# MODEM_power.net
KiCad netlist of a schematic drawn in Altium Designer
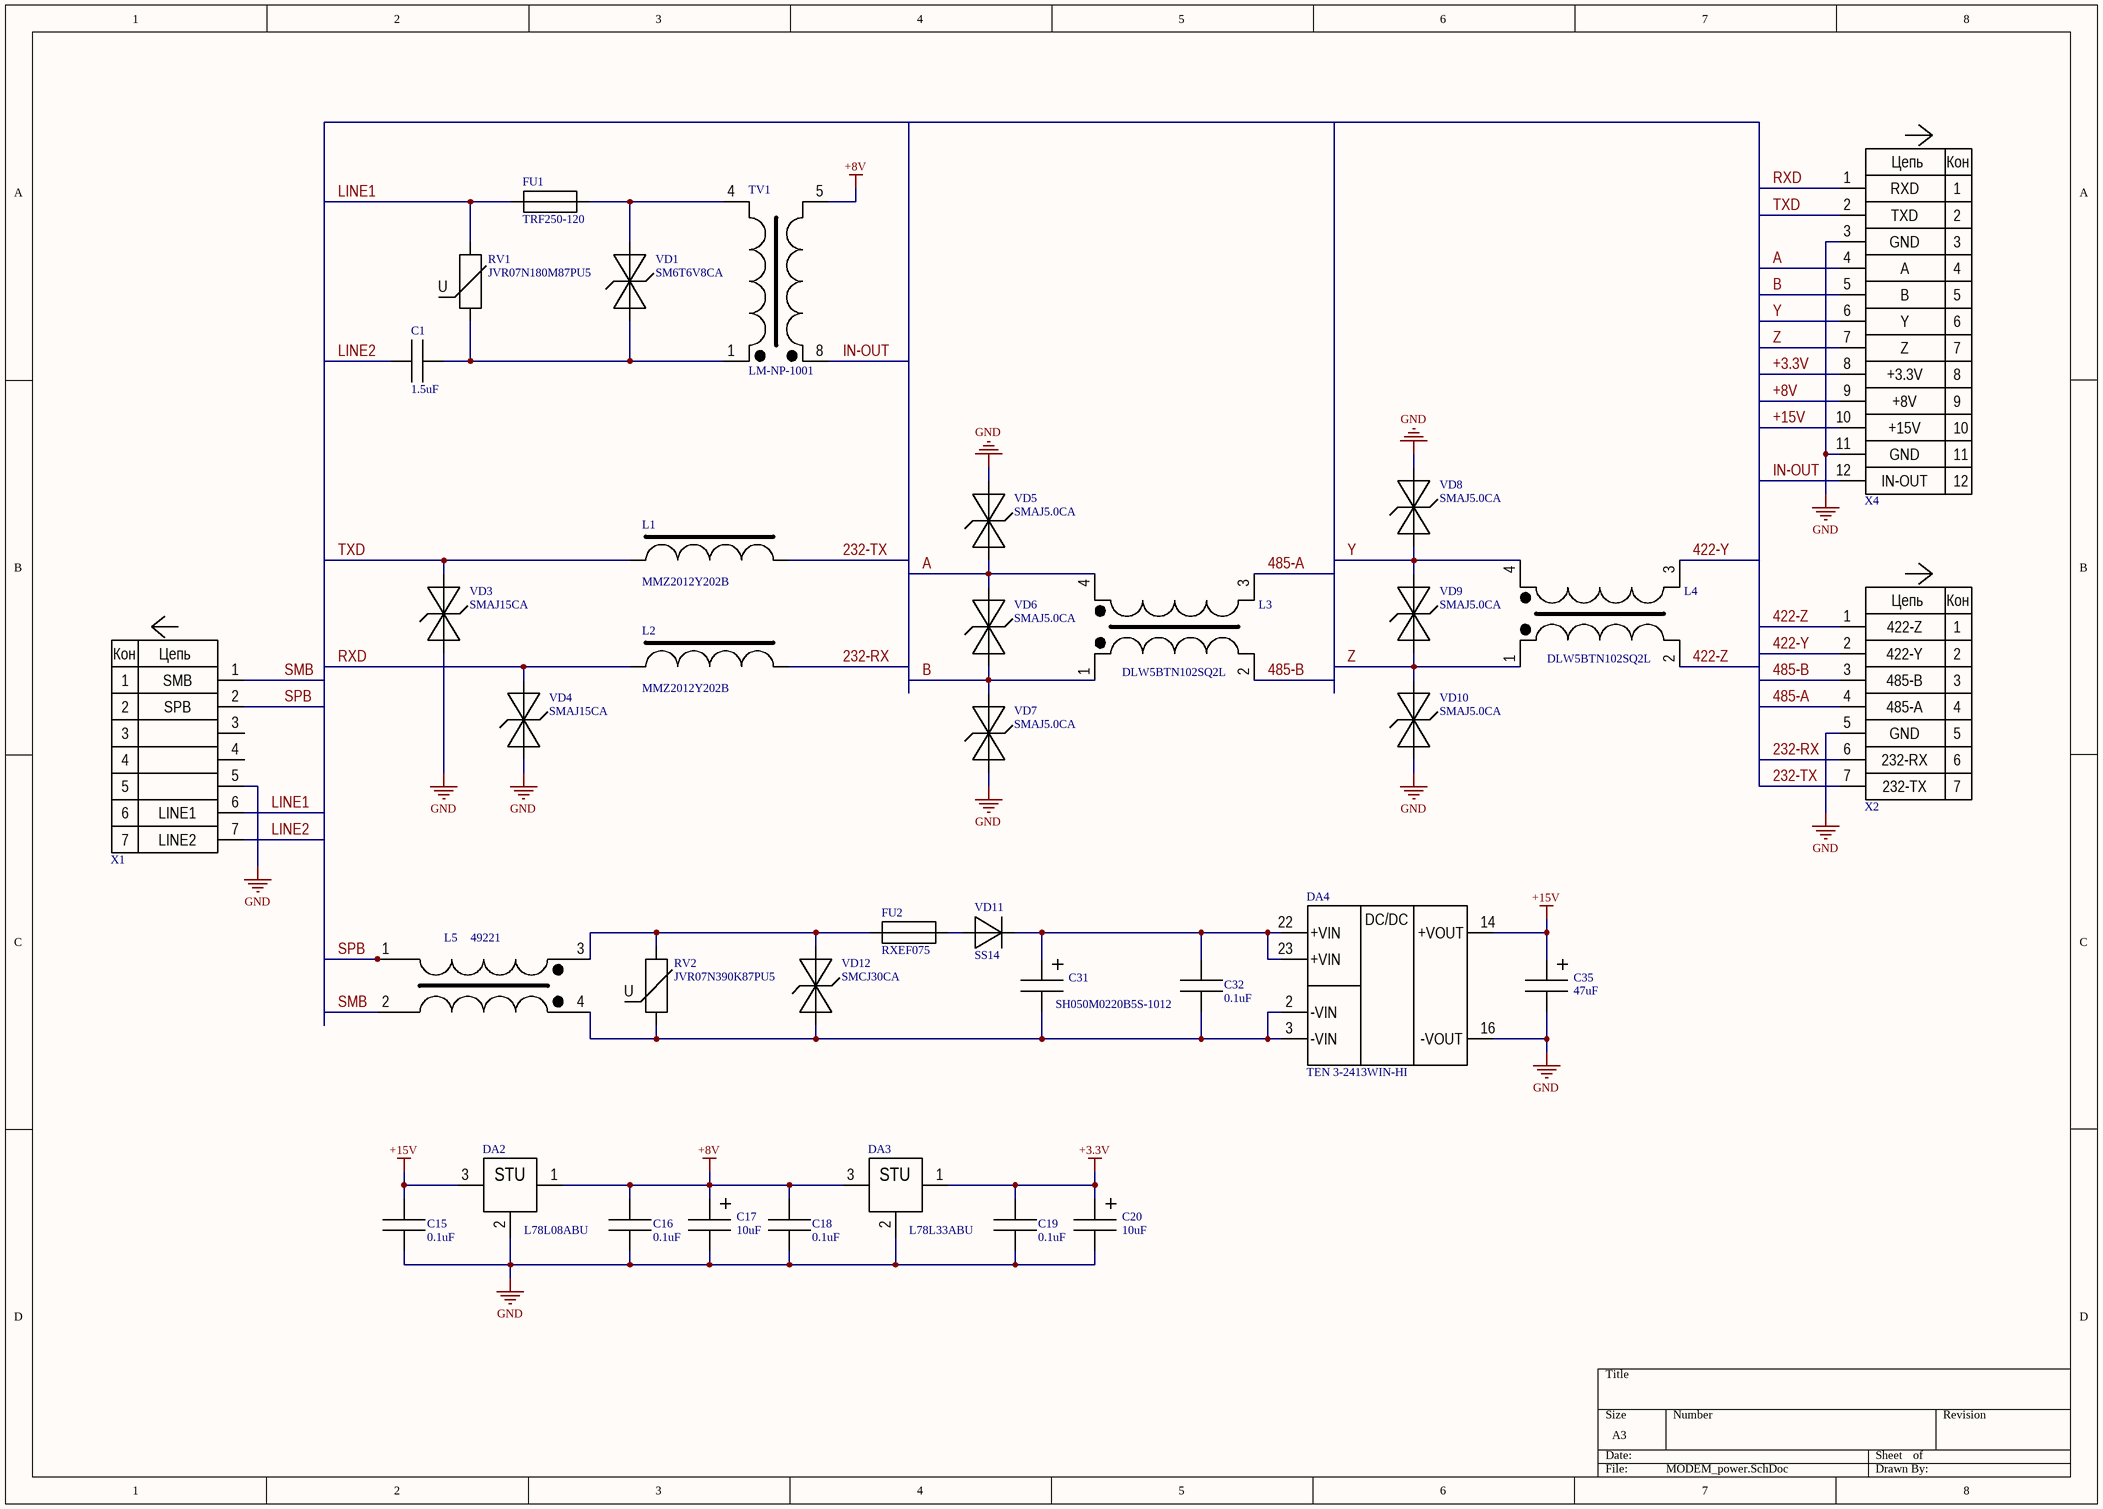
[diagram p0: MODEM_power.SchDoc]

(export (version "E")
  (design (tool "Eeschema 10.0.6"))
  (components
    (comp (ref "C1") (value "1.5uF") (footprint "TS02-22.5-h") (libsource (lib "CAPACITORS") (part "CC1206")))
    (comp (ref "C15") (value "0.1uF") (footprint "CC0805") (libsource (lib "CAPACITORS") (part "CC1206")))
    (comp (ref "C16") (value "0.1uF") (footprint "CC0805") (libsource (lib "CAPACITORS") (part "CC1206")))
    (comp (ref "C17") (value "10uF") (footprint "SMB") (libsource (lib "CAPACITORS") (part "SR-6")))
    (comp (ref "C18") (value "0.1uF") (footprint "CC0805") (libsource (lib "CAPACITORS") (part "CC1206")))
    (comp (ref "C19") (value "0.1uF") (footprint "CC0805") (libsource (lib "CAPACITORS") (part "CC1206")))
    (comp (ref "C20") (value "10uF") (footprint "SMB") (libsource (lib "CAPACITORS") (part "SR-6")))
    (comp (ref "C31")
      (value "SH050M0220B5S-1012")
      (footprint "Discr:SH050-1019")
      (libsource (lib "CAPACITORS") (part "SR-6"))
    )
    (comp (ref "C32") (value "0.1uF") (footprint "CC0805") (libsource (lib "CAPACITORS") (part "CC1206")))
    (comp (ref "C35") (value "47uF") (footprint "SMD") (libsource (lib "CAPACITORS") (part "SR-6")))
    (comp (ref "DA2") (value "L78L08ABU") (footprint "SOT-89") (libsource (lib "IC") (part "L78L08ABU")))
    (comp (ref "DA3") (value "L78L33ABU") (footprint "SOT-89") (libsource (lib "IC") (part "L78L33ABU")))
    (comp (ref "DA4")
      (value "TEN 3-2413WIN-HI")
      (footprint "TEN3-2412WIN")
      (libsource (lib "Power Supplies") (part "TEN3-2412WIN"))
    )
    (comp (ref "FU1")
      (value "TRF250-120")
      (footprint "TRF250-120")
      (libsource (lib "Discr") (part "TRF250-120"))
    )
    (comp (ref "FU2") (value "RXEF075") (footprint "RXEF075") (libsource (lib "Discr") (part "TRF250-120")))
    (comp (ref "L1")
      (value "MMZ2012Y202B")
      (footprint "MMZ2012Y202B")
      (libsource (lib "INDUCTORS") (part "MMZ2012Y202B"))
    )
    (comp (ref "L2")
      (value "MMZ2012Y202B")
      (footprint "MMZ2012Y202B")
      (libsource (lib "INDUCTORS") (part "MMZ2012Y202B"))
    )
    (comp (ref "L3")
      (value "DLW5BTN102SQ2L")
      (footprint "DLW5BTN")
      (libsource (lib "INDUCTORS") (part "DLW31SN"))
    )
    (comp (ref "L4")
      (value "DLW5BTN102SQ2L")
      (footprint "DLW5BTN")
      (libsource (lib "INDUCTORS") (part "DLW31SN"))
    )
    (comp (ref "L5") (value "49221") (footprint "49221") (libsource (lib "INDUCTORS") (part "49221")))
    (comp (ref "RV1")
      (value "JVR07N180M87PU5")
      (footprint "JVR07N330")
      (libsource (lib "Discr") (part "JVR14N361"))
    )
    (comp (ref "RV2")
      (value "JVR07N390K87PU5")
      (footprint "JVR07N330")
      (libsource (lib "Discr") (part "JVR14N361"))
    )
    (comp (ref "TV1")
      (value "LM-NP-1001")
      (footprint "LM-NP-1001")
      (libsource (lib "INDUCTORS") (part "LM-NP-1001"))
    )
    (comp (ref "VD1")
      (value "SM6T6V8CA")
      (footprint "SM6T6V8CA")
      (libsource (lib "DIODES") (part "SM6T6V8CA"))
    )
    (comp (ref "VD3")
      (value "SMAJ15CA")
      (footprint "SMAJ6.0CA")
      (libsource (lib "DIODES") (part "SMAJ6.0CA"))
    )
    (comp (ref "VD4")
      (value "SMAJ15CA")
      (footprint "SMAJ6.0CA")
      (libsource (lib "DIODES") (part "SMAJ6.0CA"))
    )
    (comp (ref "VD5")
      (value "SMAJ5.0CA")
      (footprint "SMAJ6.0CA")
      (libsource (lib "DIODES") (part "SMAJ6.0CA"))
    )
    (comp (ref "VD6")
      (value "SMAJ5.0CA")
      (footprint "SMAJ6.0CA")
      (libsource (lib "DIODES") (part "SMAJ6.0CA"))
    )
    (comp (ref "VD7")
      (value "SMAJ5.0CA")
      (footprint "SMAJ6.0CA")
      (libsource (lib "DIODES") (part "SMAJ6.0CA"))
    )
    (comp (ref "VD8")
      (value "SMAJ5.0CA")
      (footprint "SMAJ6.0CA")
      (libsource (lib "DIODES") (part "SMAJ6.0CA"))
    )
    (comp (ref "VD9")
      (value "SMAJ5.0CA")
      (footprint "SMAJ6.0CA")
      (libsource (lib "DIODES") (part "SMAJ6.0CA"))
    )
    (comp (ref "VD10")
      (value "SMAJ5.0CA")
      (footprint "SMAJ6.0CA")
      (libsource (lib "DIODES") (part "SMAJ6.0CA"))
    )
    (comp (ref "VD11") (value "SS14") (footprint "SS14") (libsource (lib "DIODES") (part "SS14")))
    (comp (ref "VD12") (value "SMCJ30CA") (footprint "SMCJ28A") (libsource (lib "DIODES") (part "SM6T6V8CA")))
    (comp (ref "X1")
      (value "8113_S/07")
      (footprint "8113_S/07")
      (libsource (lib "COMMUT") (part "8113_S/07"))
    )
    (comp (ref "X2")
      (value "8113_S/07")
      (footprint "8113_S/07")
      (libsource (lib "COMMUT") (part "8113_S/07"))
    )
    (comp (ref "X4") (value "PLS-12") (footprint "PLS-12") (libsource (lib "COMMUT") (part "PLS-12")))
  )
  (nets
    (net (code "1") (name "+3.3V") (class "Default")
      (node (ref "C19") (pin "2") (pinfunction "2_2") (pintype "passive"))
      (node (ref "C20") (pin "2") (pinfunction "A_2") (pintype "passive"))
      (node (ref "DA3") (pin "1") (pinfunction "OUT_1") (pintype "power_in"))
      (node (ref "X4") (pin "8") (pinfunction "8_8") (pintype "passive"))
    )
    (net (code "2") (name "+8V") (class "Default")
      (node (ref "C16") (pin "2") (pinfunction "2_2") (pintype "passive"))
      (node (ref "C17") (pin "2") (pinfunction "A_2") (pintype "passive"))
      (node (ref "C18") (pin "2") (pinfunction "2_2") (pintype "passive"))
      (node (ref "DA2") (pin "1") (pinfunction "OUT_1") (pintype "power_in"))
      (node (ref "DA3") (pin "3") (pinfunction "IN_3") (pintype "power_in"))
      (node (ref "TV1") (pin "5") (pinfunction "5_5") (pintype "passive"))
      (node (ref "X4") (pin "9") (pinfunction "9_9") (pintype "passive"))
    )
    (net (code "3") (name "+15V") (class "Default")
      (node (ref "C15") (pin "2") (pinfunction "2_2") (pintype "passive"))
      (node (ref "C35") (pin "2") (pinfunction "A_2") (pintype "passive"))
      (node (ref "DA2") (pin "3") (pinfunction "IN_3") (pintype "power_in"))
      (node (ref "DA4") (pin "14") (pinfunction "+VOUT_14") (pintype "power_in"))
      (node (ref "X4") (pin "10") (pinfunction "10_10") (pintype "passive"))
    )
    (net (code "4") (name "/232-RX") (class "Default")
      (node (ref "L2") (pin "2") (pinfunction "2_2") (pintype "passive"))
      (node (ref "X2") (pin "6") (pinfunction "6_6") (pintype "passive"))
    )
    (net (code "5") (name "/232-TX") (class "Default")
      (node (ref "L1") (pin "2") (pinfunction "2_2") (pintype "passive"))
      (node (ref "X2") (pin "7") (pinfunction "7_7") (pintype "passive"))
    )
    (net (code "6") (name "/422-Y") (class "Default")
      (node (ref "L4") (pin "3") (pinfunction "3_3") (pintype "passive"))
      (node (ref "X2") (pin "2") (pinfunction "2_2") (pintype "passive"))
    )
    (net (code "7") (name "/422-Z") (class "Default")
      (node (ref "L4") (pin "2") (pinfunction "2_2") (pintype "passive"))
      (node (ref "X2") (pin "1") (pinfunction "1_1") (pintype "passive"))
    )
    (net (code "8") (name "/485-A") (class "Default")
      (node (ref "L3") (pin "3") (pinfunction "3_3") (pintype "passive"))
      (node (ref "X2") (pin "4") (pinfunction "4_4") (pintype "passive"))
    )
    (net (code "9") (name "/485-B") (class "Default")
      (node (ref "L3") (pin "2") (pinfunction "2_2") (pintype "passive"))
      (node (ref "X2") (pin "3") (pinfunction "3_3") (pintype "passive"))
    )
    (net (code "10") (name "/A") (class "Default")
      (node (ref "L3") (pin "4") (pinfunction "4_4") (pintype "passive"))
      (node (ref "VD5") (pin "1") (pinfunction "A_1") (pintype "passive"))
      (node (ref "VD6") (pin "2") (pinfunction "С_2") (pintype "passive"))
      (node (ref "X4") (pin "4") (pinfunction "4_4") (pintype "passive"))
    )
    (net (code "11") (name "/B") (class "Default")
      (node (ref "L3") (pin "1") (pinfunction "1_1") (pintype "passive"))
      (node (ref "VD6") (pin "1") (pinfunction "A_1") (pintype "passive"))
      (node (ref "VD7") (pin "2") (pinfunction "С_2") (pintype "passive"))
      (node (ref "X4") (pin "5") (pinfunction "5_5") (pintype "passive"))
    )
    (net (code "12") (name "/IN-OUT") (class "Default")
      (node (ref "TV1") (pin "8") (pinfunction "8_8") (pintype "passive"))
      (node (ref "X4") (pin "12") (pinfunction "12_12") (pintype "passive"))
    )
    (net (code "13") (name "/LINE1") (class "Default")
      (node (ref "FU1") (pin "1") (pinfunction "1_1") (pintype "passive"))
      (node (ref "RV1") (pin "1") (pinfunction "1_1") (pintype "passive"))
      (node (ref "X1") (pin "6") (pinfunction "6_6") (pintype "passive"))
    )
    (net (code "14") (name "/LINE2") (class "Default")
      (node (ref "C1") (pin "1") (pinfunction "1_1") (pintype "passive"))
      (node (ref "X1") (pin "7") (pinfunction "7_7") (pintype "passive"))
    )
    (net (code "15") (name "/RXD") (class "Default")
      (node (ref "L2") (pin "1") (pinfunction "1_1") (pintype "passive"))
      (node (ref "VD4") (pin "2") (pinfunction "С_2") (pintype "passive"))
      (node (ref "X4") (pin "1") (pinfunction "1_1") (pintype "passive"))
    )
    (net (code "16") (name "/SMB") (class "Default")
      (node (ref "L5") (pin "2") (pinfunction "2_2") (pintype "passive"))
      (node (ref "X1") (pin "1") (pinfunction "1_1") (pintype "passive"))
    )
    (net (code "17") (name "/SPB") (class "Default")
      (node (ref "L5") (pin "1") (pinfunction "1_1") (pintype "passive"))
      (node (ref "X1") (pin "2") (pinfunction "2_2") (pintype "passive"))
    )
    (net (code "18") (name "/TXD") (class "Default")
      (node (ref "L1") (pin "1") (pinfunction "1_1") (pintype "passive"))
      (node (ref "VD3") (pin "2") (pinfunction "С_2") (pintype "passive"))
      (node (ref "X4") (pin "2") (pinfunction "2_2") (pintype "passive"))
    )
    (net (code "19") (name "/Y") (class "Default")
      (node (ref "L4") (pin "4") (pinfunction "4_4") (pintype "passive"))
      (node (ref "VD8") (pin "1") (pinfunction "A_1") (pintype "passive"))
      (node (ref "VD9") (pin "2") (pinfunction "С_2") (pintype "passive"))
      (node (ref "X4") (pin "6") (pinfunction "6_6") (pintype "passive"))
    )
    (net (code "20") (name "/Z") (class "Default")
      (node (ref "L4") (pin "1") (pinfunction "1_1") (pintype "passive"))
      (node (ref "VD10") (pin "2") (pinfunction "С_2") (pintype "passive"))
      (node (ref "VD9") (pin "1") (pinfunction "A_1") (pintype "passive"))
      (node (ref "X4") (pin "7") (pinfunction "7_7") (pintype "passive"))
    )
    (net (code "21") (name "GND") (class "Default")
      (node (ref "C15") (pin "1") (pinfunction "1_1") (pintype "passive"))
      (node (ref "C16") (pin "1") (pinfunction "1_1") (pintype "passive"))
      (node (ref "C17") (pin "1") (pinfunction "C_1") (pintype "passive"))
      (node (ref "C18") (pin "1") (pinfunction "1_1") (pintype "passive"))
      (node (ref "C19") (pin "1") (pinfunction "1_1") (pintype "passive"))
      (node (ref "C20") (pin "1") (pinfunction "C_1") (pintype "passive"))
      (node (ref "C35") (pin "1") (pinfunction "C_1") (pintype "passive"))
      (node (ref "DA2") (pin "2") (pinfunction "GND_2") (pintype "power_in"))
      (node (ref "DA3") (pin "2") (pinfunction "GND_2") (pintype "power_in"))
      (node (ref "DA4") (pin "16") (pinfunction "-VOUT_16") (pintype "power_in"))
      (node (ref "VD10") (pin "1") (pinfunction "A_1") (pintype "passive"))
      (node (ref "VD3") (pin "1") (pinfunction "A_1") (pintype "passive"))
      (node (ref "VD4") (pin "1") (pinfunction "A_1") (pintype "passive"))
      (node (ref "VD5") (pin "2") (pinfunction "С_2") (pintype "passive"))
      (node (ref "VD7") (pin "1") (pinfunction "A_1") (pintype "passive"))
      (node (ref "VD8") (pin "2") (pinfunction "С_2") (pintype "passive"))
      (node (ref "X1") (pin "5") (pinfunction "5_5") (pintype "passive"))
      (node (ref "X2") (pin "5") (pinfunction "5_5") (pintype "passive"))
      (node (ref "X4") (pin "11") (pinfunction "11_11") (pintype "passive"))
      (node (ref "X4") (pin "3") (pinfunction "3_3") (pintype "passive"))
    )
    (net (code "22") (name "Net-(C31-A)") (class "Default")
      (node (ref "C31") (pin "2") (pinfunction "A_2") (pintype "passive"))
      (node (ref "C32") (pin "2") (pinfunction "2_2") (pintype "passive"))
      (node (ref "DA4") (pin "22") (pinfunction "+VIN_22") (pintype "power_in"))
      (node (ref "DA4") (pin "23") (pinfunction "+VIN_23") (pintype "power_in"))
      (node (ref "VD11") (pin "2") (pinfunction "С_2") (pintype "passive"))
    )
    (net (code "23") (name "Net-(C31-C)") (class "Default")
      (node (ref "C31") (pin "1") (pinfunction "C_1") (pintype "passive"))
      (node (ref "C32") (pin "1") (pinfunction "1_1") (pintype "passive"))
      (node (ref "DA4") (pin "2") (pinfunction "-VIN_2") (pintype "power_in"))
      (node (ref "DA4") (pin "3") (pinfunction "-VIN_3") (pintype "power_in"))
      (node (ref "L5") (pin "4") (pinfunction "4_4") (pintype "passive"))
      (node (ref "RV2") (pin "2") (pinfunction "2_2") (pintype "passive"))
      (node (ref "VD12") (pin "1") (pinfunction "A_1") (pintype "passive"))
    )
    (net (code "24") (name "Net-(VD1-A)") (class "Default")
      (node (ref "C1") (pin "2") (pinfunction "2_2") (pintype "passive"))
      (node (ref "RV1") (pin "2") (pinfunction "2_2") (pintype "passive"))
      (node (ref "TV1") (pin "1") (pinfunction "1_1") (pintype "passive"))
      (node (ref "VD1") (pin "1") (pinfunction "A_1") (pintype "passive"))
    )
    (net (code "25") (name "Net-(VD1-С)") (class "Default")
      (node (ref "FU1") (pin "2") (pinfunction "2_2") (pintype "passive"))
      (node (ref "TV1") (pin "4") (pinfunction "4_4") (pintype "passive"))
      (node (ref "VD1") (pin "2") (pinfunction "С_2") (pintype "passive"))
    )
    (net (code "26") (name "Net-(VD11-A)") (class "Default")
      (node (ref "FU2") (pin "2") (pinfunction "2_2") (pintype "passive"))
      (node (ref "VD11") (pin "1") (pinfunction "A_1") (pintype "passive"))
    )
    (net (code "27") (name "Net-(VD12-С)") (class "Default")
      (node (ref "FU2") (pin "1") (pinfunction "1_1") (pintype "passive"))
      (node (ref "L5") (pin "3") (pinfunction "3_3") (pintype "passive"))
      (node (ref "RV2") (pin "1") (pinfunction "1_1") (pintype "passive"))
      (node (ref "VD12") (pin "2") (pinfunction "С_2") (pintype "passive"))
    )
    (net (code "28") (name "unconnected-(X1-Pad3)") (class "Default")
      (node (ref "X1") (pin "3") (pinfunction "3_3") (pintype "passive"))
    )
    (net (code "29") (name "unconnected-(X1-Pad4)") (class "Default")
      (node (ref "X1") (pin "4") (pinfunction "4_4") (pintype "passive"))
    )
  )
)
